# VL53L0X.net
KiCad netlist of a schematic drawn in Altium Designer
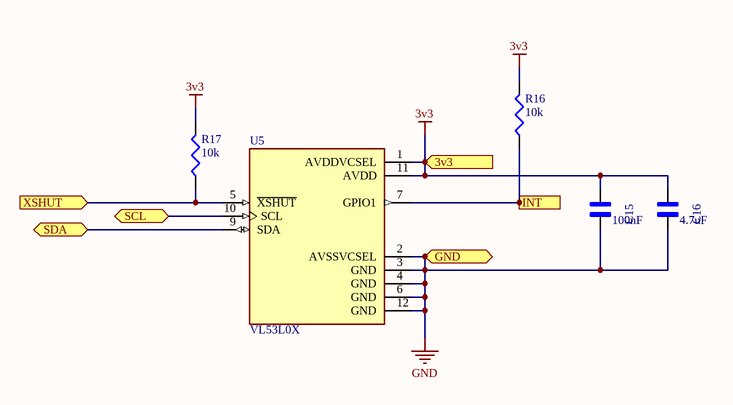
[diagram p0: VL53L0X.SchDoc]

(export (version "E")
  (design (tool "Eeschema 10.0.6"))
  (components
    (comp (ref "C15")
      (value "100nF")
      (footprint "*CAPC1608X90")
      (description "Cap Thin Film 0.1uf 50v 0603")
      (fields (field (name "MF") "AVX") (field (name "MP") "GX035C104MAT2-500 or CL10B104JB8NNNC"))
      (libsource (lib "lib") (part "GX035C104MAT2-500"))
    )
    (comp (ref "C16")
      (value "4.7uF")
      (footprint "*CAPC1608X90")
      (description "Cap Thin Film 0.1uf 50v 0603")
      (fields (field (name "MF") "AVX") (field (name "MP") "GX035C104MAT2-500 or CL10B104JB8NNNC"))
      (libsource (lib "lib") (part "GX035C104MAT2-500"))
    )
    (comp (ref "R16")
      (value "10k")
      (footprint "J1-0603")
      (description "10 kOhms 1 0.1 W 1 10 W Chip Resistor 0603 1608 Metric Thick Film")
      (fields (field (name "MF") "Yageo or NXP") (field (name "MP") "10K 1% 0603"))
      (libsource (lib "CAN_NODE_MINI") (part "RC0603FR-0710KL"))
    )
    (comp (ref "R17")
      (value "10k")
      (footprint "J1-0603")
      (description "10 kOhms 1 0.1 W 1 10 W Chip Resistor 0603 1608 Metric Thick Film")
      (fields (field (name "MF") "Yageo or NXP") (field (name "MP") "10K 1% 0603"))
      (libsource (lib "CAN_NODE_MINI") (part "RC0603FR-0710KL"))
    )
    (comp (ref "U5")
      (value "VL53L0X")
      (footprint "SENSOR_VL53L0X")
      (description "VL53L0X - Light, 3D Time-of-Flight _ToF_ Sensor Evaluation Board")
      (fields (field (name "MF") "STMicroelectronics") (field (name "DESIGNER") "Ehsan Shaghaei"))
      (libsource (lib "lib") (part "VL53L0X"))
    )
  )
  (nets
    (net (code "1") (name "/INT") (class "Default")
      (node (ref "R16") (pin "1") (pinfunction "1_1") (pintype "passive"))
      (node (ref "U5") (pin "7") (pinfunction "GPIO1_7") (pintype "output"))
    )
    (net (code "2") (name "/SCL") (class "Default")
      (node (ref "U5") (pin "10") (pinfunction "SCL_10") (pintype "input"))
    )
    (net (code "3") (name "/SDA") (class "Default")
      (node (ref "U5") (pin "9") (pinfunction "SDA_9") (pintype "bidirectional"))
    )
    (net (code "4") (name "/XSHUT") (class "Default")
      (node (ref "R17") (pin "1") (pinfunction "1_1") (pintype "passive"))
      (node (ref "U5") (pin "5") (pinfunction "~{XSHUT}_5") (pintype "input"))
    )
    (net (code "5") (name "3v3") (class "Default")
      (node (ref "C15") (pin "2") (pinfunction "2_2") (pintype "passive"))
      (node (ref "C16") (pin "2") (pinfunction "2_2") (pintype "passive"))
      (node (ref "R16") (pin "2") (pinfunction "2_2") (pintype "passive"))
      (node (ref "R17") (pin "2") (pinfunction "2_2") (pintype "passive"))
      (node (ref "U5") (pin "1") (pinfunction "AVDDVCSEL_1") (pintype "power_in"))
      (node (ref "U5") (pin "11") (pinfunction "AVDD_11") (pintype "power_in"))
    )
    (net (code "6") (name "GND") (class "Default")
      (node (ref "C15") (pin "1") (pinfunction "1_1") (pintype "passive"))
      (node (ref "C16") (pin "1") (pinfunction "1_1") (pintype "passive"))
      (node (ref "U5") (pin "12") (pinfunction "GND_12") (pintype "power_in"))
      (node (ref "U5") (pin "2") (pinfunction "AVSSVCSEL_2") (pintype "power_in"))
      (node (ref "U5") (pin "3") (pinfunction "GND_3") (pintype "power_in"))
      (node (ref "U5") (pin "4") (pinfunction "GND_4") (pintype "power_in"))
      (node (ref "U5") (pin "6") (pinfunction "GND_6") (pintype "power_in"))
    )
  )
)
